# compass.net
KiCad netlist of a schematic drawn in EAGLE
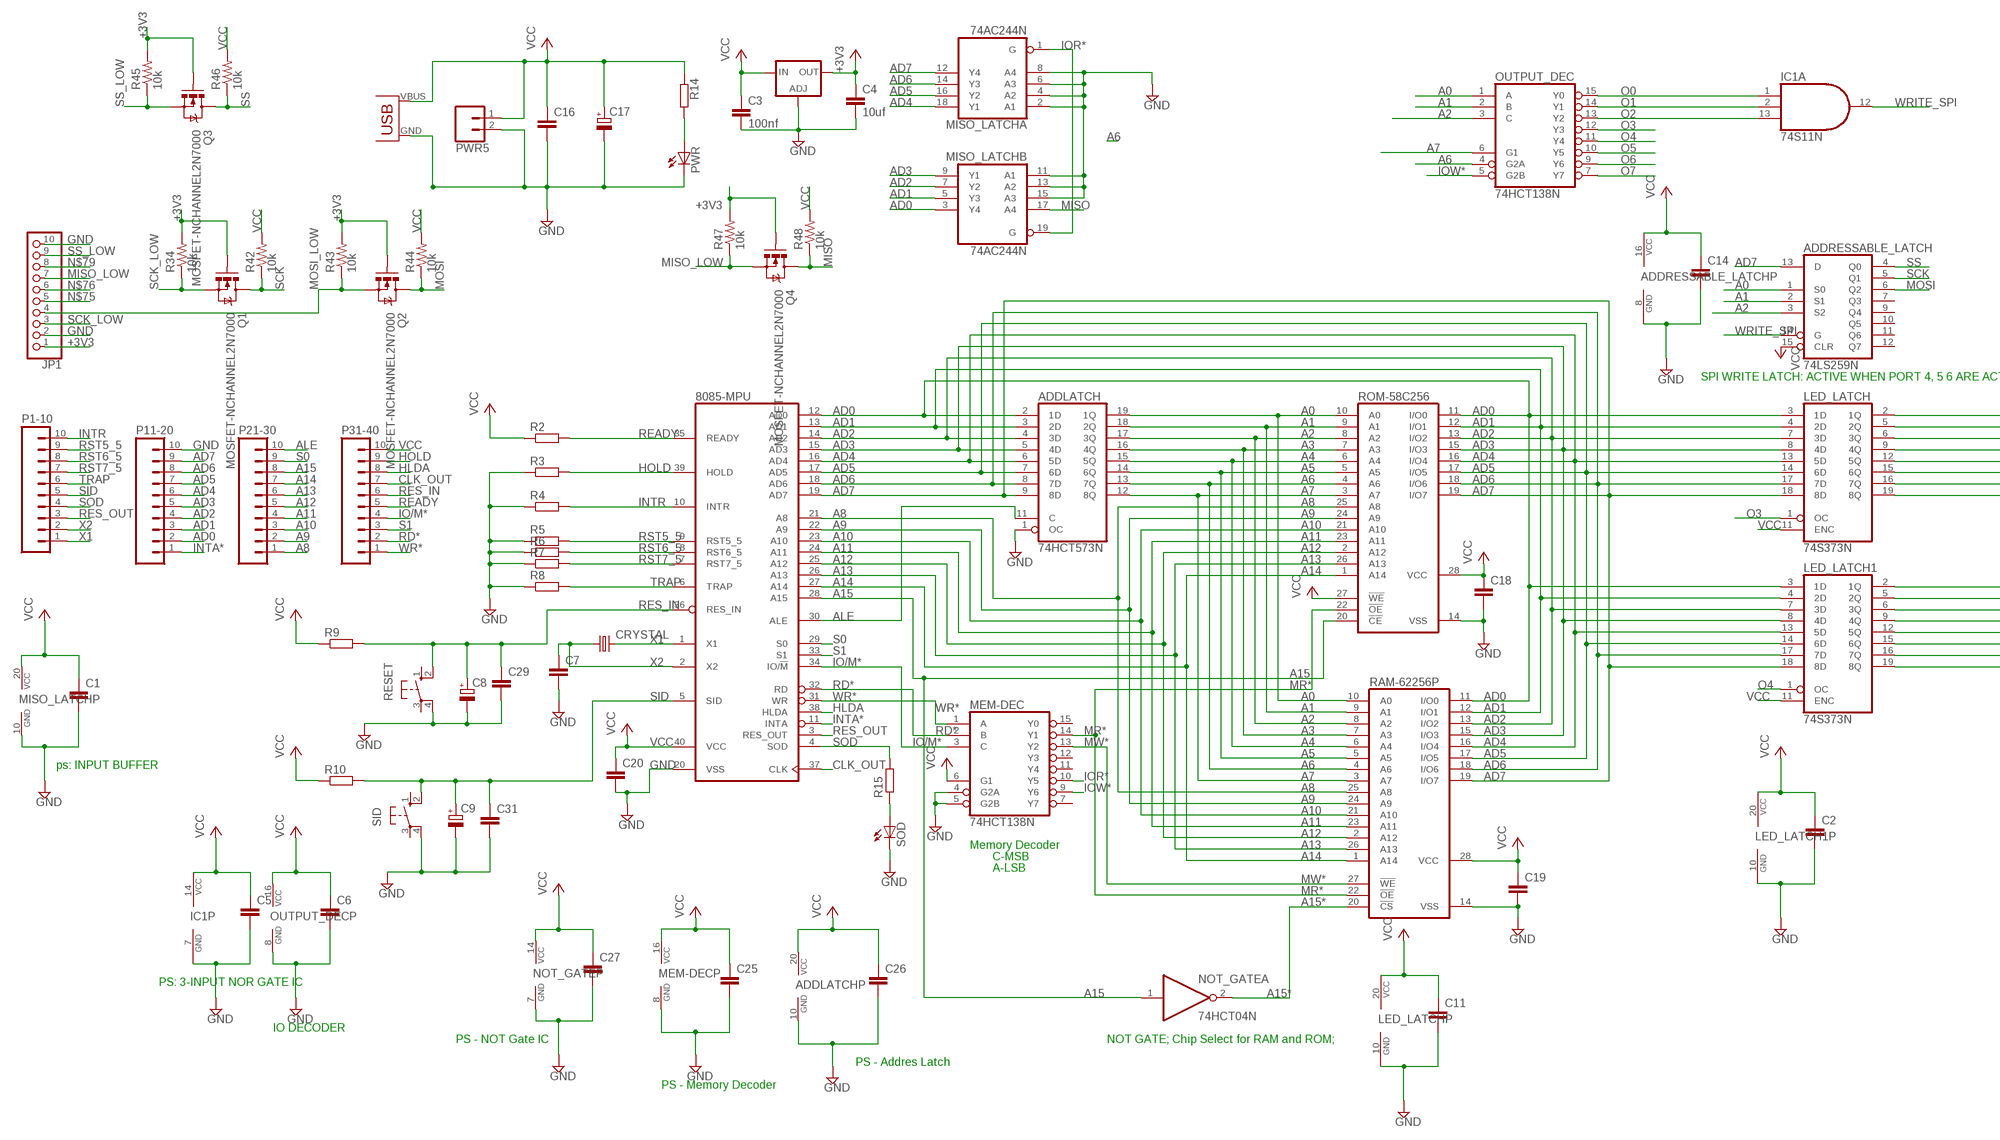
[diagram p0: schematic, sheet 1, part 1 of 2]
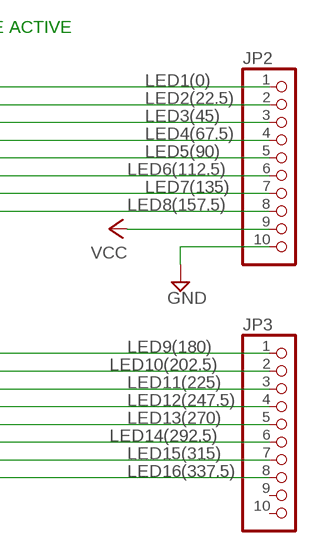
[diagram p1: schematic, sheet 1, part 2 of 2]

(export (version "E")
  (design (tool "Eeschema 10.0.6"))
  (components
    (comp (ref "8085-MPU")
      (value "8085")
      (footprint "eagle-import:DIL40")
      (libsource (lib "eagle-import") (part "8085"))
    )
    (comp (ref "ADDLATCH")
      (value "74HCT573N")
      (footprint "eagle-import:DIL20")
      (libsource (lib "eagle-import") (part "74573NHCT"))
    )
    (comp (ref "ADDRESSABLE_LATCH")
      (value "74LS259N")
      (footprint "eagle-import:DIL16")
      (libsource (lib "eagle-import") (part "74259NLS"))
    )
    (comp (ref "C1")
      (value "C-EU025-025X050")
      (footprint "eagle-import:C025-025X050")
      (libsource (lib "eagle-import") (part "resistor_C-EU025-025X050"))
    )
    (comp (ref "C2")
      (value "C-EU025-025X050")
      (footprint "eagle-import:C025-025X050")
      (libsource (lib "eagle-import") (part "resistor_C-EU025-025X050"))
    )
    (comp (ref "C3")
      (value "100nf")
      (footprint "eagle-import:C025-025X050")
      (libsource (lib "eagle-import") (part "resistor_C-EU025-025X050"))
    )
    (comp (ref "C4")
      (value "10uf")
      (footprint "eagle-import:C025-025X050")
      (libsource (lib "eagle-import") (part "resistor_C-EU025-025X050"))
    )
    (comp (ref "C5")
      (value "C-EU025-025X050")
      (footprint "eagle-import:C025-025X050")
      (libsource (lib "eagle-import") (part "resistor_C-EU025-025X050"))
    )
    (comp (ref "C6")
      (value "C-EU025-025X050")
      (footprint "eagle-import:C025-025X050")
      (libsource (lib "eagle-import") (part "resistor_C-EU025-025X050"))
    )
    (comp (ref "C7")
      (value "C-EU025-025X050")
      (footprint "eagle-import:C025-025X050")
      (libsource (lib "eagle-import") (part "C-EU025-025X050"))
    )
    (comp (ref "C8")
      (value "CPOL-EUE2.5-6")
      (footprint "eagle-import:E2,5-6")
      (libsource (lib "eagle-import") (part "CPOL-EUE2.5-6"))
    )
    (comp (ref "C9")
      (value "CPOL-EUE2.5-6")
      (footprint "eagle-import:E2,5-6")
      (libsource (lib "eagle-import") (part "CPOL-EUE2.5-6"))
    )
    (comp (ref "C11")
      (value "C-EU025-025X050")
      (footprint "eagle-import:C025-025X050")
      (libsource (lib "eagle-import") (part "resistor_C-EU025-025X050"))
    )
    (comp (ref "C14")
      (value "C-EU025-025X050")
      (footprint "eagle-import:C025-025X050")
      (libsource (lib "eagle-import") (part "resistor_C-EU025-025X050"))
    )
    (comp (ref "C16")
      (value "C-EU025-025X050")
      (footprint "eagle-import:C025-025X050")
      (libsource (lib "eagle-import") (part "resistor_C-EU025-025X050"))
    )
    (comp (ref "C17")
      (value "CPOL-EUE2.5-6")
      (footprint "eagle-import:E2,5-6")
      (libsource (lib "eagle-import") (part "CPOL-EUE2.5-6"))
    )
    (comp (ref "C18")
      (value "C-EU025-025X050")
      (footprint "eagle-import:C025-025X050")
      (libsource (lib "eagle-import") (part "resistor_C-EU025-025X050"))
    )
    (comp (ref "C19")
      (value "C-EU025-025X050")
      (footprint "eagle-import:C025-025X050")
      (libsource (lib "eagle-import") (part "resistor_C-EU025-025X050"))
    )
    (comp (ref "C20")
      (value "C-EU025-025X050")
      (footprint "eagle-import:C025-025X050")
      (libsource (lib "eagle-import") (part "resistor_C-EU025-025X050"))
    )
    (comp (ref "C25")
      (value "C-EU025-025X050")
      (footprint "eagle-import:C025-025X050")
      (libsource (lib "eagle-import") (part "resistor_C-EU025-025X050"))
    )
    (comp (ref "C26")
      (value "C-EU025-025X050")
      (footprint "eagle-import:C025-025X050")
      (libsource (lib "eagle-import") (part "resistor_C-EU025-025X050"))
    )
    (comp (ref "C27")
      (value "C-EU025-025X050")
      (footprint "eagle-import:C025-025X050")
      (libsource (lib "eagle-import") (part "resistor_C-EU025-025X050"))
    )
    (comp (ref "C29")
      (value "C-EU025-025X050")
      (footprint "eagle-import:C025-025X050")
      (libsource (lib "eagle-import") (part "C-EU025-025X050"))
    )
    (comp (ref "C31")
      (value "C-EU025-025X050")
      (footprint "eagle-import:C025-025X050")
      (libsource (lib "eagle-import") (part "C-EU025-025X050"))
    )
    (comp (ref "CRYSTAL")
      (value "CRYSTALHC49US")
      (footprint "eagle-import:HC49US")
      (libsource (lib "eagle-import") (part "CRYSTALHC49US"))
    )
    (comp (ref "IC1")
      (value "74S11N")
      (footprint "eagle-import:DIL14")
      (libsource (lib "eagle-import") (part "7411NS"))
    )
    (comp (ref "IC10")
      (value "LD117AS33TR")
      (footprint "eagle-import:SOT223")
      (libsource (lib "eagle-import") (part "LD117A?S33TR"))
    )
    (comp (ref "JP1")
      (value "PINHD-1X10")
      (footprint "eagle-import:1X10")
      (libsource (lib "eagle-import") (part "PINHD-1X10"))
    )
    (comp (ref "JP2")
      (value "PINHD-1X10")
      (footprint "eagle-import:1X10")
      (libsource (lib "eagle-import") (part "PINHD-1X10"))
    )
    (comp (ref "JP3")
      (value "PINHD-1X10")
      (footprint "eagle-import:1X10")
      (libsource (lib "eagle-import") (part "PINHD-1X10"))
    )
    (comp (ref "LED_LATCH")
      (value "74S373N")
      (footprint "eagle-import:DIL20")
      (libsource (lib "eagle-import") (part "74373NS"))
    )
    (comp (ref "LED_LATCH1")
      (value "74S373N")
      (footprint "eagle-import:DIL20")
      (libsource (lib "eagle-import") (part "74373NS"))
    )
    (comp (ref "MEM-DEC")
      (value "74HCT138N")
      (footprint "eagle-import:DIL16")
      (libsource (lib "eagle-import") (part "74138NHCT"))
    )
    (comp (ref "MISO_LATCH")
      (value "74AC244N")
      (footprint "eagle-import:DIL20")
      (libsource (lib "eagle-import") (part "74244NAC"))
    )
    (comp (ref "NOT_GATE")
      (value "74HCT04N")
      (footprint "eagle-import:DIL14")
      (libsource (lib "eagle-import") (part "7404NHCT"))
    )
    (comp (ref "OUTPUT_DEC")
      (value "74HCT138N")
      (footprint "eagle-import:DIL16")
      (libsource (lib "eagle-import") (part "74138NHCT"))
    )
    (comp (ref "P1-10")
      (value "M10")
      (footprint "eagle-import:10P")
      (libsource (lib "eagle-import") (part "M10"))
    )
    (comp (ref "P11-20")
      (value "M10")
      (footprint "eagle-import:10P")
      (libsource (lib "eagle-import") (part "M10"))
    )
    (comp (ref "P21-30")
      (value "M10")
      (footprint "eagle-import:10P")
      (libsource (lib "eagle-import") (part "M10"))
    )
    (comp (ref "P31-40")
      (value "M10")
      (footprint "eagle-import:10P")
      (libsource (lib "eagle-import") (part "M10"))
    )
    (comp (ref "PWR")
      (value "LED5MM")
      (footprint "eagle-import:LED5MM")
      (libsource (lib "eagle-import") (part "LED5MM"))
    )
    (comp (ref "PWR5")
      (value "M02")
      (footprint "eagle-import:02P")
      (libsource (lib "eagle-import") (part "M02"))
    )
    (comp (ref "Q1")
      (value "MOSFET-NCHANNEL2N7000")
      (footprint "eagle-import:TO-92")
      (libsource (lib "eagle-import") (part "MOSFET-NCHANNEL2N7000"))
    )
    (comp (ref "Q2")
      (value "MOSFET-NCHANNEL2N7000")
      (footprint "eagle-import:TO-92")
      (libsource (lib "eagle-import") (part "MOSFET-NCHANNEL2N7000"))
    )
    (comp (ref "Q3")
      (value "MOSFET-NCHANNEL2N7000")
      (footprint "eagle-import:TO-92")
      (libsource (lib "eagle-import") (part "MOSFET-NCHANNEL2N7000"))
    )
    (comp (ref "Q4")
      (value "MOSFET-NCHANNEL2N7000")
      (footprint "eagle-import:TO-92")
      (libsource (lib "eagle-import") (part "MOSFET-NCHANNEL2N7000"))
    )
    (comp (ref "R2")
      (value "R-EU_0204/7")
      (footprint "eagle-import:0204_7")
      (libsource (lib "eagle-import") (part "R-EU_0204/7"))
    )
    (comp (ref "R3")
      (value "R-EU_0204/7")
      (footprint "eagle-import:0204_7")
      (libsource (lib "eagle-import") (part "R-EU_0204/7"))
    )
    (comp (ref "R4")
      (value "R-EU_0204/7")
      (footprint "eagle-import:0204_7")
      (libsource (lib "eagle-import") (part "R-EU_0204/7"))
    )
    (comp (ref "R5")
      (value "R-EU_0204/7")
      (footprint "eagle-import:0204_7")
      (libsource (lib "eagle-import") (part "R-EU_0204/7"))
    )
    (comp (ref "R6")
      (value "R-EU_0204/7")
      (footprint "eagle-import:0204_7")
      (libsource (lib "eagle-import") (part "R-EU_0204/7"))
    )
    (comp (ref "R7")
      (value "R-EU_0204/7")
      (footprint "eagle-import:0204_7")
      (libsource (lib "eagle-import") (part "R-EU_0204/7"))
    )
    (comp (ref "R8")
      (value "R-EU_0204/7")
      (footprint "eagle-import:0204_7")
      (libsource (lib "eagle-import") (part "R-EU_0204/7"))
    )
    (comp (ref "R9")
      (value "R-EU_0204/7")
      (footprint "eagle-import:0204_7")
      (libsource (lib "eagle-import") (part "resistor_R-EU_0204/7"))
    )
    (comp (ref "R10")
      (value "R-EU_0204/7")
      (footprint "eagle-import:0204_7")
      (libsource (lib "eagle-import") (part "resistor_R-EU_0204/7"))
    )
    (comp (ref "R14")
      (value "R-EU_0204/7")
      (footprint "eagle-import:0204_7")
      (libsource (lib "eagle-import") (part "R-EU_0204/7"))
    )
    (comp (ref "R15")
      (value "R-EU_0204/7")
      (footprint "eagle-import:0204_7")
      (libsource (lib "eagle-import") (part "R-EU_0204/7"))
    )
    (comp (ref "R34")
      (value "10k")
      (footprint "eagle-import:0204_7")
      (libsource (lib "eagle-import") (part "R-US_0204/7"))
    )
    (comp (ref "R42")
      (value "10k")
      (footprint "eagle-import:0204_7")
      (libsource (lib "eagle-import") (part "R-US_0204/7"))
    )
    (comp (ref "R43")
      (value "10k")
      (footprint "eagle-import:0204_7")
      (libsource (lib "eagle-import") (part "R-US_0204/7"))
    )
    (comp (ref "R44")
      (value "10k")
      (footprint "eagle-import:0204_7")
      (libsource (lib "eagle-import") (part "R-US_0204/7"))
    )
    (comp (ref "R45")
      (value "10k")
      (footprint "eagle-import:0204_7")
      (libsource (lib "eagle-import") (part "R-US_0204/7"))
    )
    (comp (ref "R46")
      (value "10k")
      (footprint "eagle-import:0204_7")
      (libsource (lib "eagle-import") (part "R-US_0204/7"))
    )
    (comp (ref "R47")
      (value "10k")
      (footprint "eagle-import:0204_7")
      (libsource (lib "eagle-import") (part "R-US_0204/7"))
    )
    (comp (ref "R48")
      (value "10k")
      (footprint "eagle-import:0204_7")
      (libsource (lib "eagle-import") (part "R-US_0204/7"))
    )
    (comp (ref "RAM-62256P")
      (value "62256P")
      (footprint "eagle-import:DIL28-6")
      (libsource (lib "eagle-import") (part "62256P"))
    )
    (comp (ref "RESET")
      (value "10-XX")
      (footprint "eagle-import:B3F-10XX")
      (fields (field (name "MPN") "B3F-1000"))
      (libsource (lib "eagle-import") (part "10-XX"))
    )
    (comp (ref "ROM-58C256")
      (value "58C256P")
      (footprint "eagle-import:DIL28-6")
      (fields (field (name "MPN") "HN58C256AP85E"))
      (libsource (lib "eagle-import") (part "58C256P"))
    )
    (comp (ref "SID")
      (value "10-XX")
      (footprint "eagle-import:B3F-10XX")
      (fields (field (name "MPN") "B3F-1000"))
      (libsource (lib "eagle-import") (part "10-XX"))
    )
    (comp (ref "SOD")
      (value "LED5MM")
      (footprint "eagle-import:LED5MM")
      (libsource (lib "eagle-import") (part "LED5MM"))
    )
    (comp (ref "USB")
      (value "USB(POWER)")
      (footprint "eagle-import:USB(POWER)")
      (libsource (lib "eagle-import") (part "USB(POWER)"))
    )
  )
  (nets
    (net (code "1") (name "+3V3") (class "Default")
      (node (ref "C4") (pin "1") (pinfunction "1_1") (pintype "passive"))
      (node (ref "IC10") (pin "4") (pinfunction "OUT_4") (pintype "passive"))
      (node (ref "JP1") (pin "1") (pinfunction "1_1") (pintype "passive"))
      (node (ref "Q1") (pin "2") (pinfunction "G_2") (pintype "passive"))
      (node (ref "Q2") (pin "2") (pinfunction "G_2") (pintype "passive"))
      (node (ref "Q3") (pin "2") (pinfunction "G_2") (pintype "passive"))
      (node (ref "Q4") (pin "2") (pinfunction "G_2") (pintype "passive"))
      (node (ref "R34") (pin "2") (pinfunction "2_2") (pintype "passive"))
      (node (ref "R43") (pin "2") (pinfunction "2_2") (pintype "passive"))
      (node (ref "R45") (pin "2") (pinfunction "2_2") (pintype "passive"))
      (node (ref "R47") (pin "2") (pinfunction "2_2") (pintype "passive"))
    )
    (net (code "2") (name "/A0") (class "Default")
      (node (ref "ADDLATCH") (pin "19") (pinfunction "1Q_19") (pintype "tri_state"))
      (node (ref "ADDRESSABLE_LATCH") (pin "1") (pinfunction "S0_1") (pintype "input"))
      (node (ref "OUTPUT_DEC") (pin "1") (pinfunction "A_1") (pintype "input"))
      (node (ref "RAM-62256P") (pin "10") (pinfunction "A0_10") (pintype "input"))
      (node (ref "ROM-58C256") (pin "10") (pinfunction "A0_10") (pintype "input"))
    )
    (net (code "3") (name "/A1") (class "Default")
      (node (ref "ADDLATCH") (pin "18") (pinfunction "2Q_18") (pintype "tri_state"))
      (node (ref "ADDRESSABLE_LATCH") (pin "2") (pinfunction "S1_2") (pintype "input"))
      (node (ref "OUTPUT_DEC") (pin "2") (pinfunction "B_2") (pintype "input"))
      (node (ref "RAM-62256P") (pin "9") (pinfunction "A1_9") (pintype "input"))
      (node (ref "ROM-58C256") (pin "9") (pinfunction "A1_9") (pintype "input"))
    )
    (net (code "4") (name "/A2") (class "Default")
      (node (ref "ADDLATCH") (pin "17") (pinfunction "3Q_17") (pintype "tri_state"))
      (node (ref "ADDRESSABLE_LATCH") (pin "3") (pinfunction "S2_3") (pintype "input"))
      (node (ref "OUTPUT_DEC") (pin "3") (pinfunction "C_3") (pintype "input"))
      (node (ref "RAM-62256P") (pin "8") (pinfunction "A2_8") (pintype "input"))
      (node (ref "ROM-58C256") (pin "8") (pinfunction "A2_8") (pintype "input"))
    )
    (net (code "5") (name "/A3") (class "Default")
      (node (ref "ADDLATCH") (pin "16") (pinfunction "4Q_16") (pintype "tri_state"))
      (node (ref "RAM-62256P") (pin "7") (pinfunction "A3_7") (pintype "input"))
      (node (ref "ROM-58C256") (pin "7") (pinfunction "A3_7") (pintype "input"))
    )
    (net (code "6") (name "/A4") (class "Default")
      (node (ref "ADDLATCH") (pin "15") (pinfunction "5Q_15") (pintype "tri_state"))
      (node (ref "RAM-62256P") (pin "6") (pinfunction "A4_6") (pintype "input"))
      (node (ref "ROM-58C256") (pin "6") (pinfunction "A4_6") (pintype "input"))
    )
    (net (code "7") (name "/A5") (class "Default")
      (node (ref "ADDLATCH") (pin "14") (pinfunction "6Q_14") (pintype "tri_state"))
      (node (ref "RAM-62256P") (pin "5") (pinfunction "A5_5") (pintype "input"))
      (node (ref "ROM-58C256") (pin "5") (pinfunction "A5_5") (pintype "input"))
    )
    (net (code "8") (name "/A6") (class "Default")
      (node (ref "ADDLATCH") (pin "13") (pinfunction "7Q_13") (pintype "tri_state"))
      (node (ref "OUTPUT_DEC") (pin "4") (pinfunction "G2A_4") (pintype "input"))
      (node (ref "RAM-62256P") (pin "4") (pinfunction "A6_4") (pintype "input"))
      (node (ref "ROM-58C256") (pin "4") (pinfunction "A6_4") (pintype "input"))
    )
    (net (code "9") (name "/A7") (class "Default")
      (node (ref "ADDLATCH") (pin "12") (pinfunction "8Q_12") (pintype "tri_state"))
      (node (ref "OUTPUT_DEC") (pin "6") (pinfunction "G1_6") (pintype "input"))
      (node (ref "RAM-62256P") (pin "3") (pinfunction "A7_3") (pintype "input"))
      (node (ref "ROM-58C256") (pin "3") (pinfunction "A7_3") (pintype "input"))
    )
    (net (code "10") (name "/A8") (class "Default")
      (node (ref "8085-MPU") (pin "21") (pinfunction "A8_21") (pintype "output"))
      (node (ref "P21-30") (pin "1") (pinfunction "1_1") (pintype "passive"))
      (node (ref "RAM-62256P") (pin "25") (pinfunction "A8_25") (pintype "input"))
      (node (ref "ROM-58C256") (pin "25") (pinfunction "A8_25") (pintype "input"))
    )
    (net (code "11") (name "/A9") (class "Default")
      (node (ref "8085-MPU") (pin "22") (pinfunction "A9_22") (pintype "output"))
      (node (ref "P21-30") (pin "2") (pinfunction "2_2") (pintype "passive"))
      (node (ref "RAM-62256P") (pin "24") (pinfunction "A9_24") (pintype "input"))
      (node (ref "ROM-58C256") (pin "24") (pinfunction "A9_24") (pintype "input"))
    )
    (net (code "12") (name "/A10") (class "Default")
      (node (ref "8085-MPU") (pin "23") (pinfunction "A10_23") (pintype "output"))
      (node (ref "P21-30") (pin "3") (pinfunction "3_3") (pintype "passive"))
      (node (ref "RAM-62256P") (pin "21") (pinfunction "A10_21") (pintype "input"))
      (node (ref "ROM-58C256") (pin "21") (pinfunction "A10_21") (pintype "input"))
    )
    (net (code "13") (name "/A11") (class "Default")
      (node (ref "8085-MPU") (pin "24") (pinfunction "A11_24") (pintype "output"))
      (node (ref "P21-30") (pin "4") (pinfunction "4_4") (pintype "passive"))
      (node (ref "RAM-62256P") (pin "23") (pinfunction "A11_23") (pintype "input"))
      (node (ref "ROM-58C256") (pin "23") (pinfunction "A11_23") (pintype "input"))
    )
    (net (code "14") (name "/A12") (class "Default")
      (node (ref "8085-MPU") (pin "25") (pinfunction "A12_25") (pintype "output"))
      (node (ref "P21-30") (pin "5") (pinfunction "5_5") (pintype "passive"))
      (node (ref "RAM-62256P") (pin "2") (pinfunction "A12_2") (pintype "input"))
      (node (ref "ROM-58C256") (pin "2") (pinfunction "A12_2") (pintype "input"))
    )
    (net (code "15") (name "/A13") (class "Default")
      (node (ref "8085-MPU") (pin "26") (pinfunction "A13_26") (pintype "output"))
      (node (ref "P21-30") (pin "6") (pinfunction "6_6") (pintype "passive"))
      (node (ref "RAM-62256P") (pin "26") (pinfunction "A13_26") (pintype "input"))
      (node (ref "ROM-58C256") (pin "26") (pinfunction "A13_26") (pintype "input"))
    )
    (net (code "16") (name "/A14") (class "Default")
      (node (ref "8085-MPU") (pin "27") (pinfunction "A14_27") (pintype "output"))
      (node (ref "P21-30") (pin "7") (pinfunction "7_7") (pintype "passive"))
      (node (ref "RAM-62256P") (pin "1") (pinfunction "A14_1") (pintype "input"))
      (node (ref "ROM-58C256") (pin "1") (pinfunction "A14_1") (pintype "input"))
    )
    (net (code "17") (name "/A15") (class "Default")
      (node (ref "8085-MPU") (pin "28") (pinfunction "A15_28") (pintype "output"))
      (node (ref "NOT_GATE") (pin "1") (pinfunction "I_1") (pintype "input"))
      (node (ref "P21-30") (pin "8") (pinfunction "8_8") (pintype "passive"))
      (node (ref "ROM-58C256") (pin "20") (pinfunction "~{CE}_20") (pintype "input"))
    )
    (net (code "18") (name "/A15*") (class "Default")
      (node (ref "NOT_GATE") (pin "2") (pinfunction "O_2") (pintype "output"))
      (node (ref "RAM-62256P") (pin "20") (pinfunction "~{CS}_20") (pintype "input"))
    )
    (net (code "19") (name "/AD0") (class "Default")
      (node (ref "8085-MPU") (pin "12") (pinfunction "AD0_12") (pintype "bidirectional"))
      (node (ref "ADDLATCH") (pin "2") (pinfunction "1D_2") (pintype "input"))
      (node (ref "LED_LATCH") (pin "3") (pinfunction "1D_3") (pintype "input"))
      (node (ref "LED_LATCH1") (pin "3") (pinfunction "1D_3") (pintype "input"))
      (node (ref "MISO_LATCH") (pin "3") (pinfunction "Y4_3") (pintype "tri_state"))
      (node (ref "P11-20") (pin "2") (pinfunction "2_2") (pintype "passive"))
      (node (ref "RAM-62256P") (pin "11") (pinfunction "I/O0_11") (pintype "bidirectional"))
      (node (ref "ROM-58C256") (pin "11") (pinfunction "I/O0_11") (pintype "tri_state"))
    )
    (net (code "20") (name "/AD1") (class "Default")
      (node (ref "8085-MPU") (pin "13") (pinfunction "AD1_13") (pintype "bidirectional"))
      (node (ref "ADDLATCH") (pin "3") (pinfunction "2D_3") (pintype "input"))
      (node (ref "LED_LATCH") (pin "4") (pinfunction "2D_4") (pintype "input"))
      (node (ref "LED_LATCH1") (pin "4") (pinfunction "2D_4") (pintype "input"))
      (node (ref "MISO_LATCH") (pin "5") (pinfunction "Y3_5") (pintype "tri_state"))
      (node (ref "P11-20") (pin "3") (pinfunction "3_3") (pintype "passive"))
      (node (ref "RAM-62256P") (pin "12") (pinfunction "I/O1_12") (pintype "bidirectional"))
      (node (ref "ROM-58C256") (pin "12") (pinfunction "I/O1_12") (pintype "tri_state"))
    )
    (net (code "21") (name "/AD2") (class "Default")
      (node (ref "8085-MPU") (pin "14") (pinfunction "AD2_14") (pintype "bidirectional"))
      (node (ref "ADDLATCH") (pin "4") (pinfunction "3D_4") (pintype "input"))
      (node (ref "LED_LATCH") (pin "7") (pinfunction "3D_7") (pintype "input"))
      (node (ref "LED_LATCH1") (pin "7") (pinfunction "3D_7") (pintype "input"))
      (node (ref "MISO_LATCH") (pin "7") (pinfunction "Y2_7") (pintype "tri_state"))
      (node (ref "P11-20") (pin "4") (pinfunction "4_4") (pintype "passive"))
      (node (ref "RAM-62256P") (pin "13") (pinfunction "I/O2_13") (pintype "bidirectional"))
      (node (ref "ROM-58C256") (pin "13") (pinfunction "I/O2_13") (pintype "tri_state"))
    )
    (net (code "22") (name "/AD3") (class "Default")
      (node (ref "8085-MPU") (pin "15") (pinfunction "AD3_15") (pintype "bidirectional"))
      (node (ref "ADDLATCH") (pin "5") (pinfunction "4D_5") (pintype "input"))
      (node (ref "LED_LATCH") (pin "8") (pinfunction "4D_8") (pintype "input"))
      (node (ref "LED_LATCH1") (pin "8") (pinfunction "4D_8") (pintype "input"))
      (node (ref "MISO_LATCH") (pin "9") (pinfunction "Y1_9") (pintype "tri_state"))
      (node (ref "P11-20") (pin "5") (pinfunction "5_5") (pintype "passive"))
      (node (ref "RAM-62256P") (pin "15") (pinfunction "I/O3_15") (pintype "bidirectional"))
      (node (ref "ROM-58C256") (pin "15") (pinfunction "I/O3_15") (pintype "tri_state"))
    )
    (net (code "23") (name "/AD4") (class "Default")
      (node (ref "8085-MPU") (pin "16") (pinfunction "AD4_16") (pintype "bidirectional"))
      (node (ref "ADDLATCH") (pin "6") (pinfunction "5D_6") (pintype "input"))
      (node (ref "LED_LATCH") (pin "13") (pinfunction "5D_13") (pintype "input"))
      (node (ref "LED_LATCH1") (pin "13") (pinfunction "5D_13") (pintype "input"))
      (node (ref "MISO_LATCH") (pin "18") (pinfunction "Y1_18") (pintype "tri_state"))
      (node (ref "P11-20") (pin "6") (pinfunction "6_6") (pintype "passive"))
      (node (ref "RAM-62256P") (pin "16") (pinfunction "I/O4_16") (pintype "bidirectional"))
      (node (ref "ROM-58C256") (pin "16") (pinfunction "I/O4_16") (pintype "tri_state"))
    )
    (net (code "24") (name "/AD5") (class "Default")
      (node (ref "8085-MPU") (pin "17") (pinfunction "AD5_17") (pintype "bidirectional"))
      (node (ref "ADDLATCH") (pin "7") (pinfunction "6D_7") (pintype "input"))
      (node (ref "LED_LATCH") (pin "14") (pinfunction "6D_14") (pintype "input"))
      (node (ref "LED_LATCH1") (pin "14") (pinfunction "6D_14") (pintype "input"))
      (node (ref "MISO_LATCH") (pin "16") (pinfunction "Y2_16") (pintype "tri_state"))
      (node (ref "P11-20") (pin "7") (pinfunction "7_7") (pintype "passive"))
      (node (ref "RAM-62256P") (pin "17") (pinfunction "I/O5_17") (pintype "bidirectional"))
      (node (ref "ROM-58C256") (pin "17") (pinfunction "I/O5_17") (pintype "tri_state"))
    )
    (net (code "25") (name "/AD6") (class "Default")
      (node (ref "8085-MPU") (pin "18") (pinfunction "AD6_18") (pintype "bidirectional"))
      (node (ref "ADDLATCH") (pin "8") (pinfunction "7D_8") (pintype "input"))
      (node (ref "LED_LATCH") (pin "17") (pinfunction "7D_17") (pintype "input"))
      (node (ref "LED_LATCH1") (pin "17") (pinfunction "7D_17") (pintype "input"))
      (node (ref "MISO_LATCH") (pin "14") (pinfunction "Y3_14") (pintype "tri_state"))
      (node (ref "P11-20") (pin "8") (pinfunction "8_8") (pintype "passive"))
      (node (ref "RAM-62256P") (pin "18") (pinfunction "I/O6_18") (pintype "bidirectional"))
      (node (ref "ROM-58C256") (pin "18") (pinfunction "I/O6_18") (pintype "tri_state"))
    )
    (net (code "26") (name "/AD7") (class "Default")
      (node (ref "8085-MPU") (pin "19") (pinfunction "AD7_19") (pintype "bidirectional"))
      (node (ref "ADDLATCH") (pin "9") (pinfunction "8D_9") (pintype "input"))
      (node (ref "ADDRESSABLE_LATCH") (pin "13") (pinfunction "D_13") (pintype "input"))
      (node (ref "LED_LATCH") (pin "18") (pinfunction "8D_18") (pintype "input"))
      (node (ref "LED_LATCH1") (pin "18") (pinfunction "8D_18") (pintype "input"))
      (node (ref "MISO_LATCH") (pin "12") (pinfunction "Y4_12") (pintype "tri_state"))
      (node (ref "P11-20") (pin "9") (pinfunction "9_9") (pintype "passive"))
      (node (ref "RAM-62256P") (pin "19") (pinfunction "I/O7_19") (pintype "bidirectional"))
      (node (ref "ROM-58C256") (pin "19") (pinfunction "I/O7_19") (pintype "tri_state"))
    )
    (net (code "27") (name "/ALE") (class "Default")
      (node (ref "8085-MPU") (pin "30") (pinfunction "ALE_30") (pintype "output"))
      (node (ref "ADDLATCH") (pin "11") (pinfunction "C_11") (pintype "input"))
      (node (ref "P21-30") (pin "10") (pinfunction "10_10") (pintype "passive"))
    )
    (net (code "28") (name "/CLK_OUT") (class "Default")
      (node (ref "8085-MPU") (pin "37") (pinfunction "CLK_37") (pintype "output"))
      (node (ref "P31-40") (pin "7") (pinfunction "7_7") (pintype "passive"))
    )
    (net (code "29") (name "/HLDA") (class "Default")
      (node (ref "8085-MPU") (pin "38") (pinfunction "HLDA_38") (pintype "output"))
      (node (ref "P31-40") (pin "8") (pinfunction "8_8") (pintype "passive"))
    )
    (net (code "30") (name "/HOLD") (class "Default")
      (node (ref "8085-MPU") (pin "39") (pinfunction "HOLD_39") (pintype "input"))
      (node (ref "P31-40") (pin "9") (pinfunction "9_9") (pintype "passive"))
      (node (ref "R3") (pin "2") (pinfunction "2_2") (pintype "passive"))
    )
    (net (code "31") (name "/INTA*") (class "Default")
      (node (ref "8085-MPU") (pin "11") (pinfunction "INTA_11") (pintype "output"))
      (node (ref "P11-20") (pin "1") (pinfunction "1_1") (pintype "passive"))
    )
    (net (code "32") (name "/INTR") (class "Default")
      (node (ref "8085-MPU") (pin "10") (pinfunction "INTR_10") (pintype "input"))
      (node (ref "P1-10") (pin "10") (pinfunction "10_10") (pintype "passive"))
      (node (ref "R4") (pin "2") (pinfunction "2_2") (pintype "passive"))
    )
    (net (code "33") (name "/IOR*") (class "Default")
      (node (ref "MEM-DEC") (pin "10") (pinfunction "Y5_10") (pintype "output"))
      (node (ref "MISO_LATCH") (pin "1") (pinfunction "G_1") (pintype "input"))
      (node (ref "MISO_LATCH") (pin "19") (pinfunction "G_19") (pintype "input"))
    )
    (net (code "34") (name "/IOW*") (class "Default")
      (node (ref "MEM-DEC") (pin "9") (pinfunction "Y6_9") (pintype "output"))
      (node (ref "OUTPUT_DEC") (pin "5") (pinfunction "G2B_5") (pintype "input"))
    )
    (net (code "35") (name "/IO{slash}M*") (class "Default")
      (node (ref "8085-MPU") (pin "34") (pinfunction "IO/~{M}_34") (pintype "output"))
      (node (ref "MEM-DEC") (pin "3") (pinfunction "C_3") (pintype "input"))
      (node (ref "P31-40") (pin "4") (pinfunction "4_4") (pintype "passive"))
    )
    (net (code "36") (name "/LED1(0)") (class "Default")
      (node (ref "JP2") (pin "1") (pinfunction "1_1") (pintype "passive"))
      (node (ref "LED_LATCH") (pin "2") (pinfunction "1Q_2") (pintype "tri_state"))
    )
    (net (code "37") (name "/LED2(22.5)") (class "Default")
      (node (ref "JP2") (pin "2") (pinfunction "2_2") (pintype "passive"))
      (node (ref "LED_LATCH") (pin "5") (pinfunction "2Q_5") (pintype "tri_state"))
    )
    (net (code "38") (name "/LED3(45)") (class "Default")
      (node (ref "JP2") (pin "3") (pinfunction "3_3") (pintype "passive"))
      (node (ref "LED_LATCH") (pin "6") (pinfunction "3Q_6") (pintype "tri_state"))
    )
    (net (code "39") (name "/LED4(67.5)") (class "Default")
      (node (ref "JP2") (pin "4") (pinfunction "4_4") (pintype "passive"))
      (node (ref "LED_LATCH") (pin "9") (pinfunction "4Q_9") (pintype "tri_state"))
    )
    (net (code "40") (name "/LED5(90)") (class "Default")
      (node (ref "JP2") (pin "5") (pinfunction "5_5") (pintype "passive"))
      (node (ref "LED_LATCH") (pin "12") (pinfunction "5Q_12") (pintype "tri_state"))
    )
    (net (code "41") (name "/LED6(112.5)") (class "Default")
      (node (ref "JP2") (pin "6") (pinfunction "6_6") (pintype "passive"))
      (node (ref "LED_LATCH") (pin "15") (pinfunction "6Q_15") (pintype "tri_state"))
    )
    (net (code "42") (name "/LED7(135)") (class "Default")
      (node (ref "JP2") (pin "7") (pinfunction "7_7") (pintype "passive"))
      (node (ref "LED_LATCH") (pin "16") (pinfunction "7Q_16") (pintype "tri_state"))
    )
    (net (code "43") (name "/LED8(157.5)") (class "Default")
      (node (ref "JP2") (pin "8") (pinfunction "8_8") (pintype "passive"))
      (node (ref "LED_LATCH") (pin "19") (pinfunction "8Q_19") (pintype "tri_state"))
    )
    (net (code "44") (name "/LED9(180)") (class "Default")
      (node (ref "JP3") (pin "1") (pinfunction "1_1") (pintype "passive"))
      (node (ref "LED_LATCH1") (pin "2") (pinfunction "1Q_2") (pintype "tri_state"))
    )
    (net (code "45") (name "/LED10(202.5)") (class "Default")
      (node (ref "JP3") (pin "2") (pinfunction "2_2") (pintype "passive"))
      (node (ref "LED_LATCH1") (pin "5") (pinfunction "2Q_5") (pintype "tri_state"))
    )
    (net (code "46") (name "/LED11(225)") (class "Default")
      (node (ref "JP3") (pin "3") (pinfunction "3_3") (pintype "passive"))
      (node (ref "LED_LATCH1") (pin "6") (pinfunction "3Q_6") (pintype "tri_state"))
    )
    (net (code "47") (name "/LED12(247.5)") (class "Default")
      (node (ref "JP3") (pin "4") (pinfunction "4_4") (pintype "passive"))
      (node (ref "LED_LATCH1") (pin "9") (pinfunction "4Q_9") (pintype "tri_state"))
    )
    (net (code "48") (name "/LED13(270)") (class "Default")
      (node (ref "JP3") (pin "5") (pinfunction "5_5") (pintype "passive"))
      (node (ref "LED_LATCH1") (pin "12") (pinfunction "5Q_12") (pintype "tri_state"))
    )
    (net (code "49") (name "/LED14(292.5)") (class "Default")
      (node (ref "JP3") (pin "6") (pinfunction "6_6") (pintype "passive"))
      (node (ref "LED_LATCH1") (pin "15") (pinfunction "6Q_15") (pintype "tri_state"))
    )
    (net (code "50") (name "/LED15(315)") (class "Default")
      (node (ref "JP3") (pin "7") (pinfunction "7_7") (pintype "passive"))
      (node (ref "LED_LATCH1") (pin "16") (pinfunction "7Q_16") (pintype "tri_state"))
    )
    (net (code "51") (name "/LED16(337.5)") (class "Default")
      (node (ref "JP3") (pin "8") (pinfunction "8_8") (pintype "passive"))
      (node (ref "LED_LATCH1") (pin "19") (pinfunction "8Q_19") (pintype "tri_state"))
    )
    (net (code "52") (name "/MISO") (class "Default")
      (node (ref "MISO_LATCH") (pin "17") (pinfunction "A4_17") (pintype "input"))
      (node (ref "Q4") (pin "3") (pinfunction "D_3") (pintype "passive"))
      (node (ref "R48") (pin "1") (pinfunction "1_1") (pintype "passive"))
    )
    (net (code "53") (name "/MISO_LOW") (class "Default")
      (node (ref "JP1") (pin "7") (pinfunction "7_7") (pintype "passive"))
      (node (ref "Q4") (pin "1") (pinfunction "S_1") (pintype "passive"))
      (node (ref "R47") (pin "1") (pinfunction "1_1") (pintype "passive"))
    )
    (net (code "54") (name "/MOSI") (class "Default")
      (node (ref "ADDRESSABLE_LATCH") (pin "6") (pinfunction "Q2_6") (pintype "output"))
      (node (ref "Q2") (pin "3") (pinfunction "D_3") (pintype "passive"))
      (node (ref "R44") (pin "1") (pinfunction "1_1") (pintype "passive"))
    )
    (net (code "55") (name "/MOSI_LOW") (class "Default")
      (node (ref "JP1") (pin "4") (pinfunction "4_4") (pintype "passive"))
      (node (ref "Q2") (pin "1") (pinfunction "S_1") (pintype "passive"))
      (node (ref "R43") (pin "1") (pinfunction "1_1") (pintype "passive"))
    )
    (net (code "56") (name "/MR*") (class "Default")
      (node (ref "MEM-DEC") (pin "14") (pinfunction "Y1_14") (pintype "output"))
      (node (ref "RAM-62256P") (pin "22") (pinfunction "~{OE}_22") (pintype "input"))
      (node (ref "ROM-58C256") (pin "22") (pinfunction "~{OE}_22") (pintype "input"))
    )
    (net (code "57") (name "/MW*") (class "Default")
      (node (ref "MEM-DEC") (pin "13") (pinfunction "Y2_13") (pintype "output"))
      (node (ref "RAM-62256P") (pin "27") (pinfunction "~{WE}_27") (pintype "input"))
    )
    (net (code "58") (name "/N$75") (class "Default")
      (node (ref "JP1") (pin "5") (pinfunction "5_5") (pintype "passive"))
    )
    (net (code "59") (name "/N$76") (class "Default")
      (node (ref "JP1") (pin "6") (pinfunction "6_6") (pintype "passive"))
    )
    (net (code "60") (name "/N$79") (class "Default")
      (node (ref "JP1") (pin "8") (pinfunction "8_8") (pintype "passive"))
    )
    (net (code "61") (name "/O0") (class "Default")
      (node (ref "IC1") (pin "1") (pinfunction "I0_1") (pintype "input"))
      (node (ref "OUTPUT_DEC") (pin "15") (pinfunction "Y0_15") (pintype "output"))
    )
    (net (code "62") (name "/O1") (class "Default")
      (node (ref "IC1") (pin "2") (pinfunction "I1_2") (pintype "input"))
      (node (ref "OUTPUT_DEC") (pin "14") (pinfunction "Y1_14") (pintype "output"))
    )
    (net (code "63") (name "/O2") (class "Default")
      (node (ref "IC1") (pin "13") (pinfunction "I2_13") (pintype "input"))
      (node (ref "OUTPUT_DEC") (pin "13") (pinfunction "Y2_13") (pintype "output"))
    )
    (net (code "64") (name "/O3") (class "Default")
      (node (ref "LED_LATCH") (pin "1") (pinfunction "OC_1") (pintype "input"))
      (node (ref "OUTPUT_DEC") (pin "12") (pinfunction "Y3_12") (pintype "output"))
    )
    (net (code "65") (name "/O4") (class "Default")
      (node (ref "LED_LATCH1") (pin "1") (pinfunction "OC_1") (pintype "input"))
      (node (ref "OUTPUT_DEC") (pin "11") (pinfunction "Y4_11") (pintype "output"))
    )
    (net (code "66") (name "/O5") (class "Default")
      (node (ref "OUTPUT_DEC") (pin "10") (pinfunction "Y5_10") (pintype "output"))
    )
    (net (code "67") (name "/O6") (class "Default")
      (node (ref "OUTPUT_DEC") (pin "9") (pinfunction "Y6_9") (pintype "output"))
    )
    (net (code "68") (name "/O7") (class "Default")
      (node (ref "OUTPUT_DEC") (pin "7") (pinfunction "Y7_7") (pintype "output"))
    )
    (net (code "69") (name "/RD*") (class "Default")
      (node (ref "8085-MPU") (pin "32") (pinfunction "RD_32") (pintype "output"))
      (node (ref "MEM-DEC") (pin "2") (pinfunction "B_2") (pintype "input"))
      (node (ref "P31-40") (pin "2") (pinfunction "2_2") (pintype "passive"))
    )
    (net (code "70") (name "/READY") (class "Default")
      (node (ref "8085-MPU") (pin "35") (pinfunction "READY_35") (pintype "input"))
      (node (ref "P31-40") (pin "5") (pinfunction "5_5") (pintype "passive"))
      (node (ref "R2") (pin "2") (pinfunction "2_2") (pintype "passive"))
    )
    (net (code "71") (name "/RES_IN") (class "Default")
      (node (ref "8085-MPU") (pin "36") (pinfunction "RES_IN_36") (pintype "input"))
      (node (ref "C29") (pin "1") (pinfunction "1_1") (pintype "passive"))
      (node (ref "C8") (pin "+") (pinfunction "+_+") (pintype "passive"))
      (node (ref "P31-40") (pin "6") (pinfunction "6_6") (pintype "passive"))
      (node (ref "R9") (pin "2") (pinfunction "2_2") (pintype "passive"))
      (node (ref "RESET") (pin "2") (pinfunction "S1_2") (pintype "passive"))
    )
    (net (code "72") (name "/RES_OUT") (class "Default")
      (node (ref "8085-MPU") (pin "3") (pinfunction "RES_OUT_3") (pintype "output"))
      (node (ref "P1-10") (pin "3") (pinfunction "3_3") (pintype "passive"))
    )
    (net (code "73") (name "/RST5_5") (class "Default")
      (node (ref "8085-MPU") (pin "9") (pinfunction "RST5_5_9") (pintype "input"))
      (node (ref "P1-10") (pin "9") (pinfunction "9_9") (pintype "passive"))
      (node (ref "R5") (pin "2") (pinfunction "2_2") (pintype "passive"))
    )
    (net (code "74") (name "/RST6_5") (class "Default")
      (node (ref "8085-MPU") (pin "8") (pinfunction "RST6_5_8") (pintype "input"))
      (node (ref "P1-10") (pin "8") (pinfunction "8_8") (pintype "passive"))
      (node (ref "R6") (pin "2") (pinfunction "2_2") (pintype "passive"))
    )
    (net (code "75") (name "/RST7_5") (class "Default")
      (node (ref "8085-MPU") (pin "7") (pinfunction "RST7_5_7") (pintype "input"))
      (node (ref "P1-10") (pin "7") (pinfunction "7_7") (pintype "passive"))
      (node (ref "R7") (pin "2") (pinfunction "2_2") (pintype "passive"))
    )
    (net (code "76") (name "/S0") (class "Default")
      (node (ref "8085-MPU") (pin "29") (pinfunction "S0_29") (pintype "output"))
      (node (ref "P21-30") (pin "9") (pinfunction "9_9") (pintype "passive"))
    )
    (net (code "77") (name "/S1") (class "Default")
      (node (ref "8085-MPU") (pin "33") (pinfunction "S1_33") (pintype "output"))
      (node (ref "P31-40") (pin "3") (pinfunction "3_3") (pintype "passive"))
    )
    (net (code "78") (name "/SCK") (class "Default")
      (node (ref "ADDRESSABLE_LATCH") (pin "5") (pinfunction "Q1_5") (pintype "output"))
      (node (ref "Q1") (pin "3") (pinfunction "D_3") (pintype "passive"))
      (node (ref "R42") (pin "1") (pinfunction "1_1") (pintype "passive"))
    )
    (net (code "79") (name "/SCK_LOW") (class "Default")
      (node (ref "JP1") (pin "3") (pinfunction "3_3") (pintype "passive"))
      (node (ref "Q1") (pin "1") (pinfunction "S_1") (pintype "passive"))
      (node (ref "R34") (pin "1") (pinfunction "1_1") (pintype "passive"))
    )
    (net (code "80") (name "/SID") (class "Default")
      (node (ref "8085-MPU") (pin "5") (pinfunction "SID_5") (pintype "input"))
      (node (ref "C31") (pin "1") (pinfunction "1_1") (pintype "passive"))
      (node (ref "C9") (pin "+") (pinfunction "+_+") (pintype "passive"))
      (node (ref "P1-10") (pin "5") (pinfunction "5_5") (pintype "passive"))
      (node (ref "R10") (pin "2") (pinfunction "2_2") (pintype "passive"))
      (node (ref "SID") (pin "2") (pinfunction "S1_2") (pintype "passive"))
    )
    (net (code "81") (name "/SOD") (class "Default")
      (node (ref "8085-MPU") (pin "4") (pinfunction "SOD_4") (pintype "output"))
      (node (ref "P1-10") (pin "4") (pinfunction "4_4") (pintype "passive"))
      (node (ref "R15") (pin "2") (pinfunction "2_2") (pintype "passive"))
    )
    (net (code "82") (name "/SS") (class "Default")
      (node (ref "ADDRESSABLE_LATCH") (pin "4") (pinfunction "Q0_4") (pintype "output"))
      (node (ref "Q3") (pin "3") (pinfunction "D_3") (pintype "passive"))
      (node (ref "R46") (pin "1") (pinfunction "1_1") (pintype "passive"))
    )
    (net (code "83") (name "/SS_LOW") (class "Default")
      (node (ref "JP1") (pin "9") (pinfunction "9_9") (pintype "passive"))
      (node (ref "Q3") (pin "1") (pinfunction "S_1") (pintype "passive"))
      (node (ref "R45") (pin "1") (pinfunction "1_1") (pintype "passive"))
    )
    (net (code "84") (name "/TRAP") (class "Default")
      (node (ref "8085-MPU") (pin "6") (pinfunction "TRAP_6") (pintype "input"))
      (node (ref "P1-10") (pin "6") (pinfunction "6_6") (pintype "passive"))
      (node (ref "R8") (pin "2") (pinfunction "2_2") (pintype "passive"))
    )
    (net (code "85") (name "/WR*") (class "Default")
      (node (ref "8085-MPU") (pin "31") (pinfunction "WR_31") (pintype "output"))
      (node (ref "MEM-DEC") (pin "1") (pinfunction "A_1") (pintype "input"))
      (node (ref "P31-40") (pin "1") (pinfunction "1_1") (pintype "passive"))
    )
    (net (code "86") (name "/WRITE_SPI") (class "Default")
      (node (ref "ADDRESSABLE_LATCH") (pin "14") (pinfunction "G_14") (pintype "input"))
      (node (ref "IC1") (pin "12") (pinfunction "O_12") (pintype "output"))
    )
    (net (code "87") (name "/X1") (class "Default")
      (node (ref "8085-MPU") (pin "1") (pinfunction "X1_1") (pintype "input"))
      (node (ref "CRYSTAL") (pin "2") (pinfunction "2_2") (pintype "passive"))
      (node (ref "P1-10") (pin "1") (pinfunction "1_1") (pintype "passive"))
    )
    (net (code "88") (name "/X2") (class "Default")
      (node (ref "8085-MPU") (pin "2") (pinfunction "X2_2") (pintype "input"))
      (node (ref "C7") (pin "1") (pinfunction "1_1") (pintype "passive"))
      (node (ref "CRYSTAL") (pin "1") (pinfunction "1_1") (pintype "passive"))
      (node (ref "P1-10") (pin "2") (pinfunction "2_2") (pintype "passive"))
    )
    (net (code "89") (name "GND") (class "Default")
      (node (ref "8085-MPU") (pin "20") (pinfunction "VSS_20") (pintype "power_in"))
      (node (ref "ADDLATCH") (pin "1") (pinfunction "OC_1") (pintype "input"))
      (node (ref "ADDLATCH") (pin "10") (pinfunction "GND_10") (pintype "power_in"))
      (node (ref "ADDRESSABLE_LATCH") (pin "8") (pinfunction "GND_8") (pintype "power_in"))
      (node (ref "C1") (pin "2") (pinfunction "2_2") (pintype "passive"))
      (node (ref "C11") (pin "2") (pinfunction "2_2") (pintype "passive"))
      (node (ref "C14") (pin "2") (pinfunction "2_2") (pintype "passive"))
      (node (ref "C16") (pin "2") (pinfunction "2_2") (pintype "passive"))
      (node (ref "C17") (pin "-") (pinfunction "-_-") (pintype "passive"))
      (node (ref "C18") (pin "2") (pinfunction "2_2") (pintype "passive"))
      (node (ref "C19") (pin "2") (pinfunction "2_2") (pintype "passive"))
      (node (ref "C2") (pin "2") (pinfunction "2_2") (pintype "passive"))
      (node (ref "C20") (pin "2") (pinfunction "2_2") (pintype "passive"))
      (node (ref "C25") (pin "2") (pinfunction "2_2") (pintype "passive"))
      (node (ref "C26") (pin "2") (pinfunction "2_2") (pintype "passive"))
      (node (ref "C27") (pin "2") (pinfunction "2_2") (pintype "passive"))
      (node (ref "C29") (pin "2") (pinfunction "2_2") (pintype "passive"))
      (node (ref "C3") (pin "2") (pinfunction "2_2") (pintype "passive"))
      (node (ref "C31") (pin "2") (pinfunction "2_2") (pintype "passive"))
      (node (ref "C4") (pin "2") (pinfunction "2_2") (pintype "passive"))
      (node (ref "C5") (pin "2") (pinfunction "2_2") (pintype "passive"))
      (node (ref "C6") (pin "2") (pinfunction "2_2") (pintype "passive"))
      (node (ref "C7") (pin "2") (pinfunction "2_2") (pintype "passive"))
      (node (ref "C8") (pin "-") (pinfunction "-_-") (pintype "passive"))
      (node (ref "C9") (pin "-") (pinfunction "-_-") (pintype "passive"))
      (node (ref "IC1") (pin "7") (pinfunction "GND_7") (pintype "power_in"))
      (node (ref "IC10") (pin "1") (pinfunction "ADJ_1") (pintype "input"))
      (node (ref "JP1") (pin "10") (pinfunction "10_10") (pintype "passive"))
      (node (ref "JP1") (pin "2") (pinfunction "2_2") (pintype "passive"))
      (node (ref "JP2") (pin "10") (pinfunction "10_10") (pintype "passive"))
      (node (ref "LED_LATCH") (pin "10") (pinfunction "GND_10") (pintype "power_in"))
      (node (ref "LED_LATCH1") (pin "10") (pinfunction "GND_10") (pintype "power_in"))
      (node (ref "MEM-DEC") (pin "4") (pinfunction "G2A_4") (pintype "input"))
      (node (ref "MEM-DEC") (pin "5") (pinfunction "G2B_5") (pintype "input"))
      (node (ref "MEM-DEC") (pin "8") (pinfunction "GND_8") (pintype "power_in"))
      (node (ref "MISO_LATCH") (pin "10") (pinfunction "GND_10") (pintype "power_in"))
      (node (ref "MISO_LATCH") (pin "11") (pinfunction "A1_11") (pintype "input"))
      (node (ref "MISO_LATCH") (pin "13") (pinfunction "A2_13") (pintype "input"))
      (node (ref "MISO_LATCH") (pin "15") (pinfunction "A3_15") (pintype "input"))
      (node (ref "MISO_LATCH") (pin "2") (pinfunction "A1_2") (pintype "input"))
      (node (ref "MISO_LATCH") (pin "4") (pinfunction "A2_4") (pintype "input"))
      (node (ref "MISO_LATCH") (pin "6") (pinfunction "A3_6") (pintype "input"))
      (node (ref "MISO_LATCH") (pin "8") (pinfunction "A4_8") (pintype "input"))
      (node (ref "NOT_GATE") (pin "7") (pinfunction "GND_7") (pintype "power_in"))
      (node (ref "OUTPUT_DEC") (pin "8") (pinfunction "GND_8") (pintype "power_in"))
      (node (ref "P11-20") (pin "10") (pinfunction "10_10") (pintype "passive"))
      (node (ref "PWR") (pin "K") (pinfunction "C_K") (pintype "passive"))
      (node (ref "PWR5") (pin "2") (pinfunction "2_2") (pintype "passive"))
      (node (ref "R3") (pin "1") (pinfunction "1_1") (pintype "passive"))
      (node (ref "R4") (pin "1") (pinfunction "1_1") (pintype "passive"))
      (node (ref "R5") (pin "1") (pinfunction "1_1") (pintype "passive"))
      (node (ref "R6") (pin "1") (pinfunction "1_1") (pintype "passive"))
      (node (ref "R7") (pin "1") (pinfunction "1_1") (pintype "passive"))
      (node (ref "R8") (pin "1") (pinfunction "1_1") (pintype "passive"))
      (node (ref "RAM-62256P") (pin "14") (pinfunction "VSS_14") (pintype "power_in"))
      (node (ref "RESET") (pin "4") (pinfunction "P1_4") (pintype "passive"))
      (node (ref "ROM-58C256") (pin "14") (pinfunction "VSS_14") (pintype "power_in"))
      (node (ref "SID") (pin "4") (pinfunction "P1_4") (pintype "passive"))
      (node (ref "SOD") (pin "K") (pinfunction "C_K") (pintype "passive"))
      (node (ref "USB") (pin "GND") (pinfunction "GND_GND") (pintype "power_in"))
    )
    (net (code "90") (name "Net-(PWR-PadA)") (class "Default")
      (node (ref "PWR") (pin "A") (pinfunction "A_A") (pintype "passive"))
      (node (ref "R14") (pin "2") (pinfunction "2_2") (pintype "passive"))
    )
    (net (code "91") (name "Net-(R15-Pad1)") (class "Default")
      (node (ref "R15") (pin "1") (pinfunction "1_1") (pintype "passive"))
      (node (ref "SOD") (pin "A") (pinfunction "A_A") (pintype "passive"))
    )
    (net (code "92") (name "VCC") (class "Default")
      (node (ref "8085-MPU") (pin "40") (pinfunction "VCC_40") (pintype "power_in"))
      (node (ref "ADDLATCH") (pin "20") (pinfunction "VCC_20") (pintype "power_in"))
      (node (ref "ADDRESSABLE_LATCH") (pin "15") (pinfunction "CLR_15") (pintype "input"))
      (node (ref "ADDRESSABLE_LATCH") (pin "16") (pinfunction "VCC_16") (pintype "power_in"))
      (node (ref "C1") (pin "1") (pinfunction "1_1") (pintype "passive"))
      (node (ref "C11") (pin "1") (pinfunction "1_1") (pintype "passive"))
      (node (ref "C14") (pin "1") (pinfunction "1_1") (pintype "passive"))
      (node (ref "C16") (pin "1") (pinfunction "1_1") (pintype "passive"))
      (node (ref "C17") (pin "+") (pinfunction "+_+") (pintype "passive"))
      (node (ref "C18") (pin "1") (pinfunction "1_1") (pintype "passive"))
      (node (ref "C19") (pin "1") (pinfunction "1_1") (pintype "passive"))
      (node (ref "C2") (pin "1") (pinfunction "1_1") (pintype "passive"))
      (node (ref "C20") (pin "1") (pinfunction "1_1") (pintype "passive"))
      (node (ref "C25") (pin "1") (pinfunction "1_1") (pintype "passive"))
      (node (ref "C26") (pin "1") (pinfunction "1_1") (pintype "passive"))
      (node (ref "C27") (pin "1") (pinfunction "1_1") (pintype "passive"))
      (node (ref "C3") (pin "1") (pinfunction "1_1") (pintype "passive"))
      (node (ref "C5") (pin "1") (pinfunction "1_1") (pintype "passive"))
      (node (ref "C6") (pin "1") (pinfunction "1_1") (pintype "passive"))
      (node (ref "IC1") (pin "14") (pinfunction "VCC_14") (pintype "power_in"))
      (node (ref "IC10") (pin "3") (pinfunction "IN_3") (pintype "input"))
      (node (ref "JP2") (pin "9") (pinfunction "9_9") (pintype "passive"))
      (node (ref "LED_LATCH") (pin "11") (pinfunction "ENC_11") (pintype "input"))
      (node (ref "LED_LATCH") (pin "20") (pinfunction "VCC_20") (pintype "power_in"))
      (node (ref "LED_LATCH1") (pin "11") (pinfunction "ENC_11") (pintype "input"))
      (node (ref "LED_LATCH1") (pin "20") (pinfunction "VCC_20") (pintype "power_in"))
      (node (ref "MEM-DEC") (pin "16") (pinfunction "VCC_16") (pintype "power_in"))
      (node (ref "MEM-DEC") (pin "6") (pinfunction "G1_6") (pintype "input"))
      (node (ref "MISO_LATCH") (pin "20") (pinfunction "VCC_20") (pintype "power_in"))
      (node (ref "NOT_GATE") (pin "14") (pinfunction "VCC_14") (pintype "power_in"))
      (node (ref "OUTPUT_DEC") (pin "16") (pinfunction "VCC_16") (pintype "power_in"))
      (node (ref "P31-40") (pin "10") (pinfunction "10_10") (pintype "passive"))
      (node (ref "PWR5") (pin "1") (pinfunction "1_1") (pintype "passive"))
      (node (ref "R10") (pin "1") (pinfunction "1_1") (pintype "passive"))
      (node (ref "R14") (pin "1") (pinfunction "1_1") (pintype "passive"))
      (node (ref "R2") (pin "1") (pinfunction "1_1") (pintype "passive"))
      (node (ref "R42") (pin "2") (pinfunction "2_2") (pintype "passive"))
      (node (ref "R44") (pin "2") (pinfunction "2_2") (pintype "passive"))
      (node (ref "R46") (pin "2") (pinfunction "2_2") (pintype "passive"))
      (node (ref "R48") (pin "2") (pinfunction "2_2") (pintype "passive"))
      (node (ref "R9") (pin "1") (pinfunction "1_1") (pintype "passive"))
      (node (ref "RAM-62256P") (pin "28") (pinfunction "VCC_28") (pintype "power_in"))
      (node (ref "ROM-58C256") (pin "27") (pinfunction "~{WE}_27") (pintype "input"))
      (node (ref "ROM-58C256") (pin "28") (pinfunction "VCC_28") (pintype "power_in"))
      (node (ref "USB") (pin "VBUS") (pinfunction "VCC_VBUS") (pintype "power_in"))
    )
    (net (code "93") (name "unconnected-(ADDRESSABLE_LATCHA-Q3-Pad7)") (class "Default")
      (node (ref "ADDRESSABLE_LATCH") (pin "7") (pinfunction "Q3_7") (pintype "output"))
    )
    (net (code "94") (name "unconnected-(ADDRESSABLE_LATCHA-Q4-Pad9)") (class "Default")
      (node (ref "ADDRESSABLE_LATCH") (pin "9") (pinfunction "Q4_9") (pintype "output"))
    )
    (net (code "95") (name "unconnected-(ADDRESSABLE_LATCHA-Q5-Pad10)") (class "Default")
      (node (ref "ADDRESSABLE_LATCH") (pin "10") (pinfunction "Q5_10") (pintype "output"))
    )
    (net (code "96") (name "unconnected-(ADDRESSABLE_LATCHA-Q6-Pad11)") (class "Default")
      (node (ref "ADDRESSABLE_LATCH") (pin "11") (pinfunction "Q6_11") (pintype "output"))
    )
    (net (code "97") (name "unconnected-(ADDRESSABLE_LATCHA-Q7-Pad12)") (class "Default")
      (node (ref "ADDRESSABLE_LATCH") (pin "12") (pinfunction "Q7_12") (pintype "output"))
    )
    (net (code "98") (name "unconnected-(JP3-Pad9)") (class "Default")
      (node (ref "JP3") (pin "9") (pinfunction "9_9") (pintype "passive"))
    )
    (net (code "99") (name "unconnected-(JP3-Pad10)") (class "Default")
      (node (ref "JP3") (pin "10") (pinfunction "10_10") (pintype "passive"))
    )
    (net (code "100") (name "unconnected-(MEM-DECA-Y0-Pad15)") (class "Default")
      (node (ref "MEM-DEC") (pin "15") (pinfunction "Y0_15") (pintype "output"))
    )
    (net (code "101") (name "unconnected-(MEM-DECA-Y3-Pad12)") (class "Default")
      (node (ref "MEM-DEC") (pin "12") (pinfunction "Y3_12") (pintype "output"))
    )
    (net (code "102") (name "unconnected-(MEM-DECA-Y4-Pad11)") (class "Default")
      (node (ref "MEM-DEC") (pin "11") (pinfunction "Y4_11") (pintype "output"))
    )
    (net (code "103") (name "unconnected-(MEM-DECA-Y7-Pad7)") (class "Default")
      (node (ref "MEM-DEC") (pin "7") (pinfunction "Y7_7") (pintype "output"))
    )
    (net (code "104") (name "unconnected-(RESET-P-Pad3)") (class "Default")
      (node (ref "RESET") (pin "3") (pinfunction "P_3") (pintype "passive"))
    )
    (net (code "105") (name "unconnected-(RESET-S-Pad1)") (class "Default")
      (node (ref "RESET") (pin "1") (pinfunction "S_1") (pintype "passive"))
    )
    (net (code "106") (name "unconnected-(SID-P-Pad3)") (class "Default")
      (node (ref "SID") (pin "3") (pinfunction "P_3") (pintype "passive"))
    )
    (net (code "107") (name "unconnected-(SID-S-Pad1)") (class "Default")
      (node (ref "SID") (pin "1") (pinfunction "S_1") (pintype "passive"))
    )
  )
)
